# ATTINY44_breakout.net
KiCad netlist of a schematic drawn in EAGLE
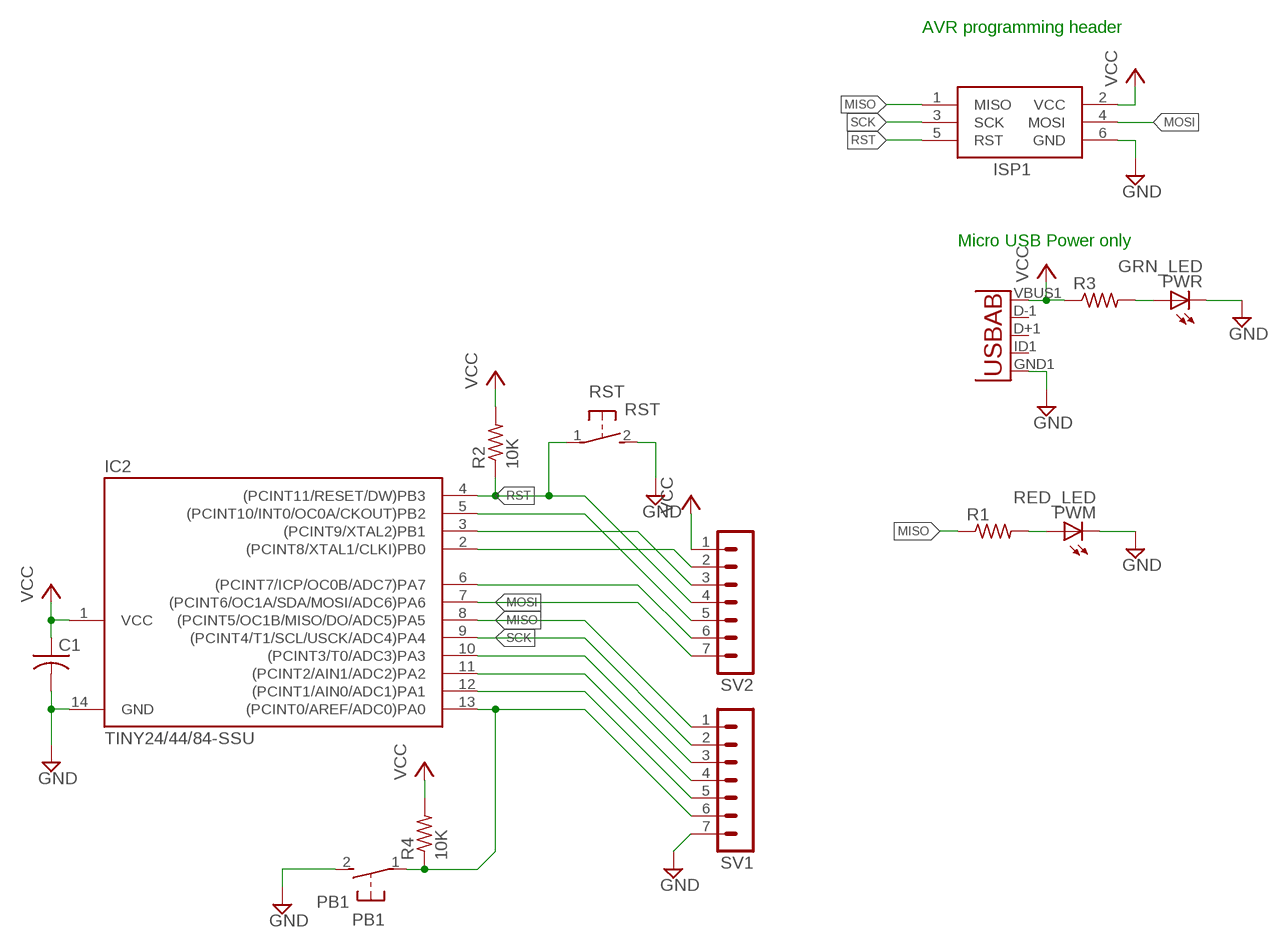
[diagram p0: schematic, sheet 1]

(export (version "E")
  (design (tool "Eeschema 10.0.6"))
  (components
    (comp (ref "C1")
      (value "C-USC0805")
      (footprint "eagle-import:C0805")
      (libsource (lib "eagle-import") (part "C-USC0805"))
    )
    (comp (ref "IC2")
      (value "TINY24/44/84-SSU")
      (footprint "eagle-import:SOIC14")
      (libsource (lib "eagle-import") (part "TINY24/44/84-SSU"))
    )
    (comp (ref "ISP1")
      (value "AVRISP-6")
      (footprint "eagle-import:AVRISP")
      (libsource (lib "eagle-import") (part "AVRISP-6"))
    )
    (comp (ref "PB1")
      (value "PB1")
      (footprint "eagle-import:DTSM-3")
      (libsource (lib "eagle-import") (part "DTSM-3"))
    )
    (comp (ref "PWM")
      (value "RED_LED")
      (footprint "eagle-import:CHIPLED_0805")
      (libsource (lib "eagle-import") (part "LEDCHIPLED_0805"))
    )
    (comp (ref "PWR")
      (value "GRN_LED")
      (footprint "eagle-import:CHIPLED_0805")
      (libsource (lib "eagle-import") (part "LEDCHIPLED_0805"))
    )
    (comp (ref "R1")
      (value "R-US_R0805")
      (footprint "eagle-import:R0805")
      (libsource (lib "eagle-import") (part "R-US_R0805"))
    )
    (comp (ref "R2")
      (value "10K")
      (footprint "eagle-import:R0805")
      (libsource (lib "eagle-import") (part "R-US_R0805"))
    )
    (comp (ref "R3")
      (value "R-US_R0805")
      (footprint "eagle-import:R0805")
      (libsource (lib "eagle-import") (part "R-US_R0805"))
    )
    (comp (ref "R4")
      (value "10K")
      (footprint "eagle-import:R0805")
      (libsource (lib "eagle-import") (part "R-US_R0805"))
    )
    (comp (ref "RST")
      (value "RST")
      (footprint "eagle-import:DTSM-3")
      (libsource (lib "eagle-import") (part "DTSM-3"))
    )
    (comp (ref "SV1")
      (value "MA07-1")
      (footprint "eagle-import:MA07-1")
      (libsource (lib "eagle-import") (part "MA07-1"))
    )
    (comp (ref "SV2")
      (value "MA07-1")
      (footprint "eagle-import:MA07-1")
      (libsource (lib "eagle-import") (part "MA07-1"))
    )
    (comp (ref "U1")
      (value "USB\"\"")
      (footprint "eagle-import:USB-MICRO-SMD")
      (libsource (lib "eagle-import") (part "USB{dblquote}{dblquote}"))
    )
  )
  (nets
    (net (code "1") (name "GND") (class "Default")
      (node (ref "C1") (pin "2") (pinfunction "2_2") (pintype "passive"))
      (node (ref "IC2") (pin "14") (pinfunction "GND_14") (pintype "power_in"))
      (node (ref "ISP1") (pin "6") (pinfunction "GND_6") (pintype "power_in"))
      (node (ref "PB1") (pin "2") (pinfunction "2_2") (pintype "passive"))
      (node (ref "PWM") (pin "C") (pinfunction "C_C") (pintype "passive"))
      (node (ref "PWR") (pin "C") (pinfunction "C_C") (pintype "passive"))
      (node (ref "RST") (pin "2") (pinfunction "2_2") (pintype "passive"))
      (node (ref "SV1") (pin "7") (pinfunction "7_7") (pintype "passive"))
      (node (ref "U1") (pin "GND1") (pinfunction "GND_GND1") (pintype "bidirectional"))
    )
    (net (code "2") (name "MISO") (class "Default")
      (node (ref "IC2") (pin "8") (pinfunction "(PCINT5/OC1B/MISO/DO/ADC5)PA5_8") (pintype "bidirectional"))
      (node (ref "ISP1") (pin "1") (pinfunction "MISO_1") (pintype "input"))
      (node (ref "R1") (pin "1") (pinfunction "1_1") (pintype "passive"))
      (node (ref "SV1") (pin "1") (pinfunction "1_1") (pintype "passive"))
    )
    (net (code "3") (name "MOSI") (class "Default")
      (node (ref "IC2") (pin "7") (pinfunction "(PCINT6/OC1A/SDA/MOSI/ADC6)PA6_7") (pintype "bidirectional"))
      (node (ref "ISP1") (pin "4") (pinfunction "MOSI_4") (pintype "output"))
      (node (ref "SV2") (pin "7") (pinfunction "7_7") (pintype "passive"))
    )
    (net (code "4") (name "Net-(IC2-(PCINT0{slash}AREF{slash}ADC0)PA0)") (class "Default")
      (node (ref "IC2") (pin "13") (pinfunction "(PCINT0/AREF/ADC0)PA0_13") (pintype "bidirectional"))
      (node (ref "PB1") (pin "1") (pinfunction "1_1") (pintype "passive"))
      (node (ref "R4") (pin "1") (pinfunction "1_1") (pintype "passive"))
      (node (ref "SV1") (pin "6") (pinfunction "6_6") (pintype "passive"))
    )
    (net (code "5") (name "Net-(IC2-(PCINT1{slash}AIN0{slash}ADC1)PA1)") (class "Default")
      (node (ref "IC2") (pin "12") (pinfunction "(PCINT1/AIN0/ADC1)PA1_12") (pintype "bidirectional"))
      (node (ref "SV1") (pin "5") (pinfunction "5_5") (pintype "passive"))
    )
    (net (code "6") (name "Net-(IC2-(PCINT2{slash}AIN1{slash}ADC2)PA2)") (class "Default")
      (node (ref "IC2") (pin "11") (pinfunction "(PCINT2/AIN1/ADC2)PA2_11") (pintype "bidirectional"))
      (node (ref "SV1") (pin "4") (pinfunction "4_4") (pintype "passive"))
    )
    (net (code "7") (name "Net-(IC2-(PCINT3{slash}T0{slash}ADC3)PA3)") (class "Default")
      (node (ref "IC2") (pin "10") (pinfunction "(PCINT3/T0/ADC3)PA3_10") (pintype "bidirectional"))
      (node (ref "SV1") (pin "3") (pinfunction "3_3") (pintype "passive"))
    )
    (net (code "8") (name "Net-(IC2-(PCINT7{slash}ICP{slash}OC0B{slash}ADC7)PA7)") (class "Default")
      (node (ref "IC2") (pin "6") (pinfunction "(PCINT7/ICP/OC0B/ADC7)PA7_6") (pintype "bidirectional"))
      (node (ref "SV2") (pin "6") (pinfunction "6_6") (pintype "passive"))
    )
    (net (code "9") (name "Net-(IC2-(PCINT8{slash}XTAL1{slash}CLKI)PB0)") (class "Default")
      (node (ref "IC2") (pin "2") (pinfunction "(PCINT8/XTAL1/CLKI)PB0_2") (pintype "bidirectional"))
      (node (ref "SV2") (pin "2") (pinfunction "2_2") (pintype "passive"))
    )
    (net (code "10") (name "Net-(IC2-(PCINT9{slash}XTAL2)PB1)") (class "Default")
      (node (ref "IC2") (pin "3") (pinfunction "(PCINT9/XTAL2)PB1_3") (pintype "bidirectional"))
      (node (ref "SV2") (pin "3") (pinfunction "3_3") (pintype "passive"))
    )
    (net (code "11") (name "Net-(IC2-(PCINT10{slash}INT0{slash}OC0A{slash}CKOUT)PB2)") (class "Default")
      (node (ref "IC2") (pin "5") (pinfunction "(PCINT10/INT0/OC0A/CKOUT)PB2_5") (pintype "bidirectional"))
      (node (ref "SV2") (pin "5") (pinfunction "5_5") (pintype "passive"))
    )
    (net (code "12") (name "Net-(PWM-PadA)") (class "Default")
      (node (ref "PWM") (pin "A") (pinfunction "A_A") (pintype "passive"))
      (node (ref "R1") (pin "2") (pinfunction "2_2") (pintype "passive"))
    )
    (net (code "13") (name "Net-(PWR-PadA)") (class "Default")
      (node (ref "PWR") (pin "A") (pinfunction "A_A") (pintype "passive"))
      (node (ref "R3") (pin "2") (pinfunction "2_2") (pintype "passive"))
    )
    (net (code "14") (name "RST") (class "Default")
      (node (ref "IC2") (pin "4") (pinfunction "(PCINT11/RESET/DW)PB3_4") (pintype "bidirectional"))
      (node (ref "ISP1") (pin "5") (pinfunction "RST_5") (pintype "output"))
      (node (ref "R2") (pin "1") (pinfunction "1_1") (pintype "passive"))
      (node (ref "RST") (pin "1") (pinfunction "1_1") (pintype "passive"))
      (node (ref "SV2") (pin "4") (pinfunction "4_4") (pintype "passive"))
    )
    (net (code "15") (name "SCK") (class "Default")
      (node (ref "IC2") (pin "9") (pinfunction "(PCINT4/T1/SCL/USCK/ADC4)PA4_9") (pintype "bidirectional"))
      (node (ref "ISP1") (pin "3") (pinfunction "SCK_3") (pintype "output"))
      (node (ref "SV1") (pin "2") (pinfunction "2_2") (pintype "passive"))
    )
    (net (code "16") (name "VCC") (class "Default")
      (node (ref "C1") (pin "1") (pinfunction "1_1") (pintype "passive"))
      (node (ref "IC2") (pin "1") (pinfunction "VCC_1") (pintype "power_in"))
      (node (ref "ISP1") (pin "2") (pinfunction "VCC_2") (pintype "power_in"))
      (node (ref "R2") (pin "2") (pinfunction "2_2") (pintype "passive"))
      (node (ref "R3") (pin "1") (pinfunction "1_1") (pintype "passive"))
      (node (ref "R4") (pin "2") (pinfunction "2_2") (pintype "passive"))
      (node (ref "SV2") (pin "1") (pinfunction "1_1") (pintype "passive"))
      (node (ref "U1") (pin "VBUS1") (pinfunction "VBUS_VBUS1") (pintype "bidirectional"))
    )
    (net (code "17") (name "unconnected-(U1-D+-PadD+1)") (class "Default")
      (node (ref "U1") (pin "D+1") (pinfunction "D+_D+1") (pintype "bidirectional"))
    )
    (net (code "18") (name "unconnected-(U1-D--PadD-1)") (class "Default")
      (node (ref "U1") (pin "D-1") (pinfunction "D-_D-1") (pintype "bidirectional"))
    )
    (net (code "19") (name "unconnected-(U1-USBID-PadID1)") (class "Default")
      (node (ref "U1") (pin "ID1") (pinfunction "USBID_ID1") (pintype "bidirectional"))
    )
  )
)
